# record_revb.net
KiCad netlist of a schematic drawn in EAGLE
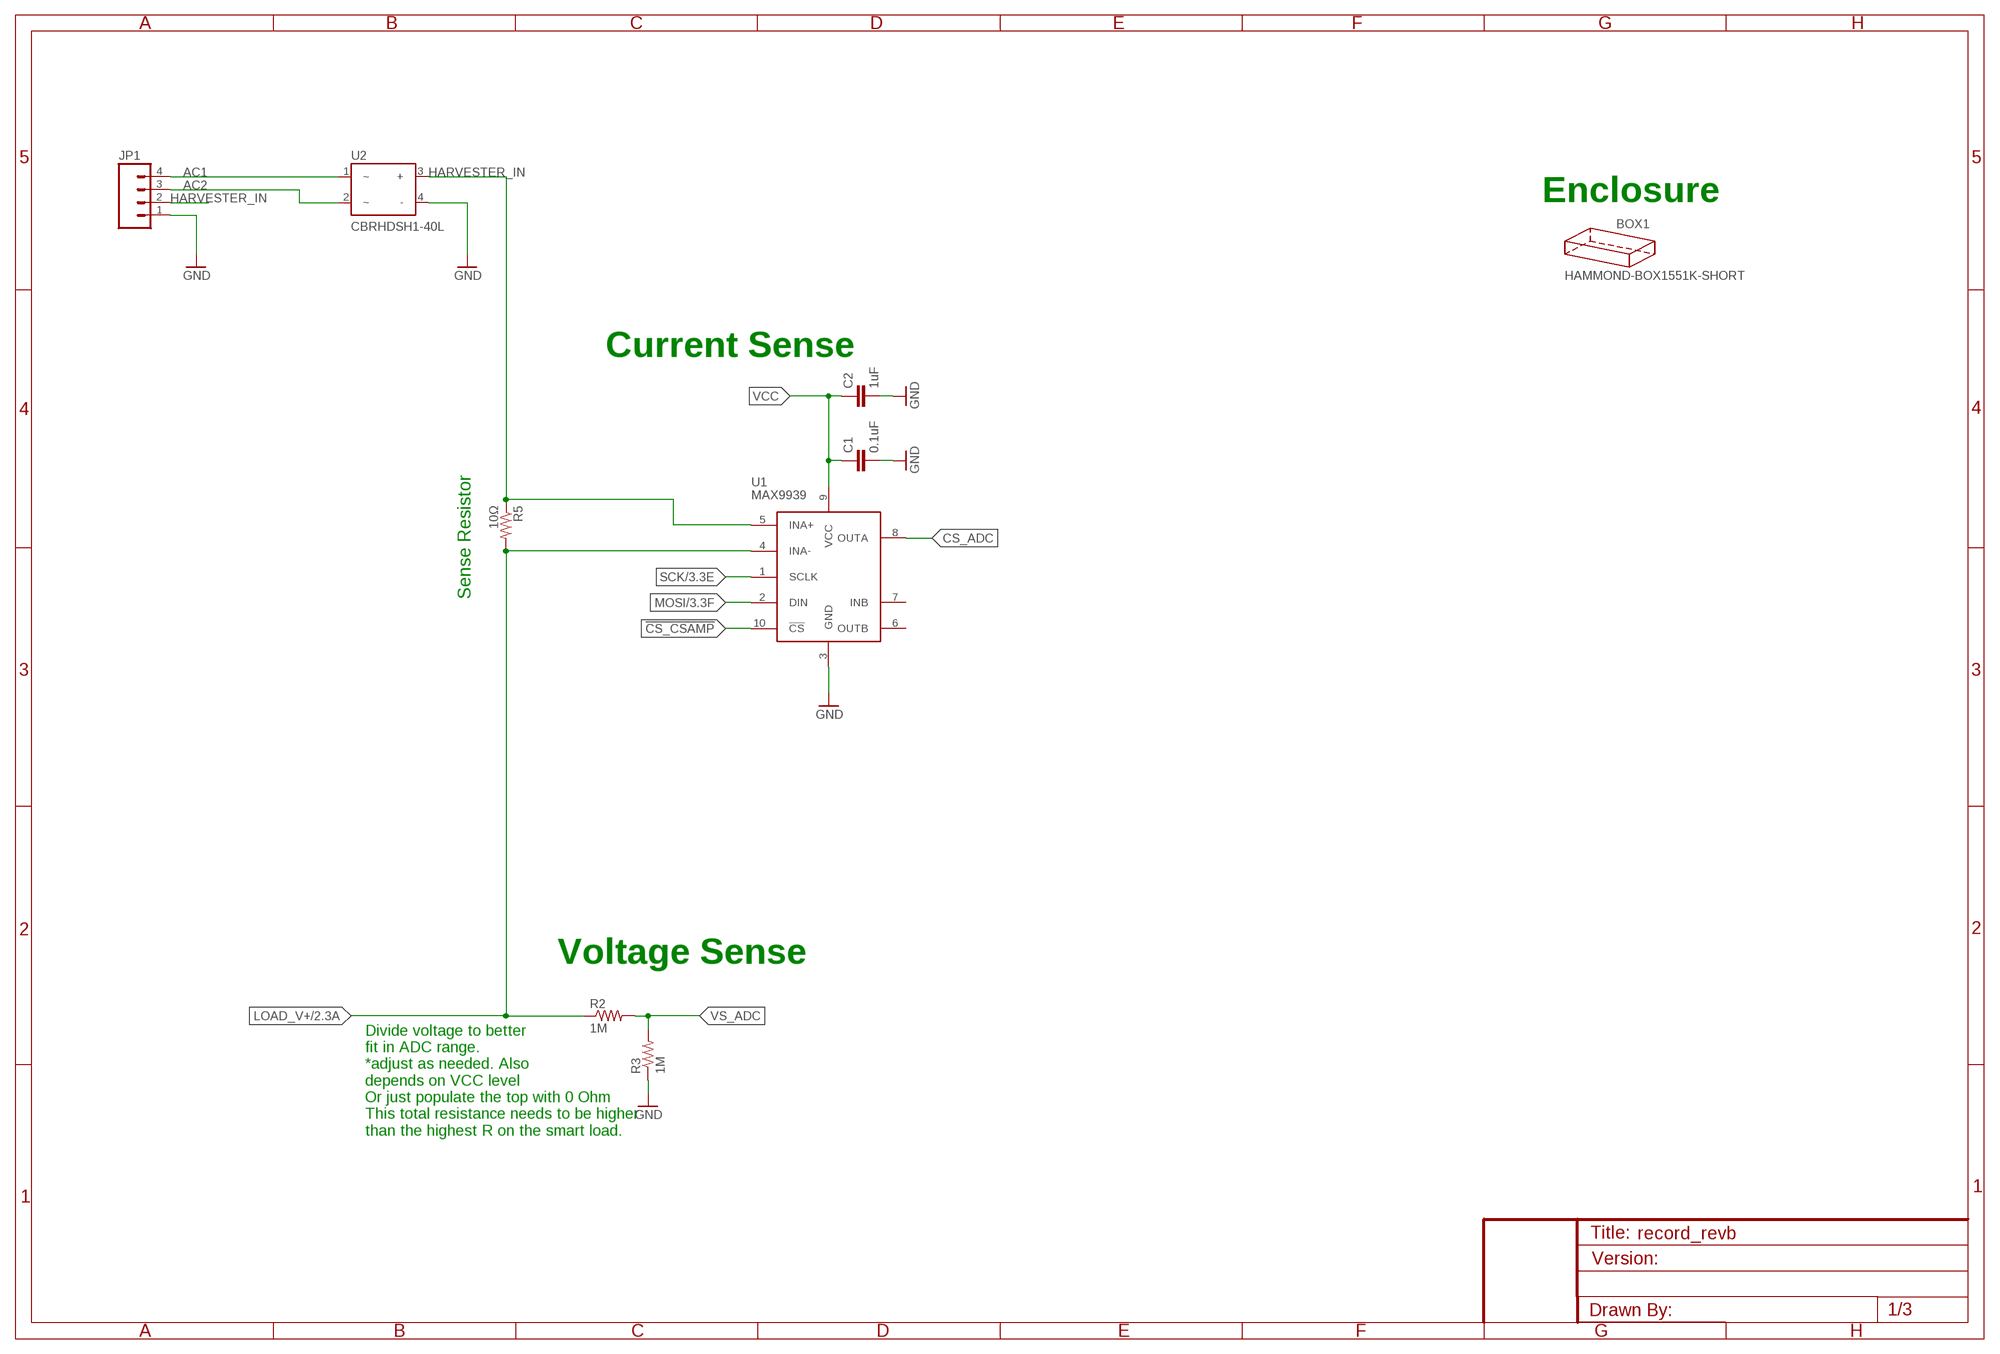
[diagram p0: schematic, sheet 1]
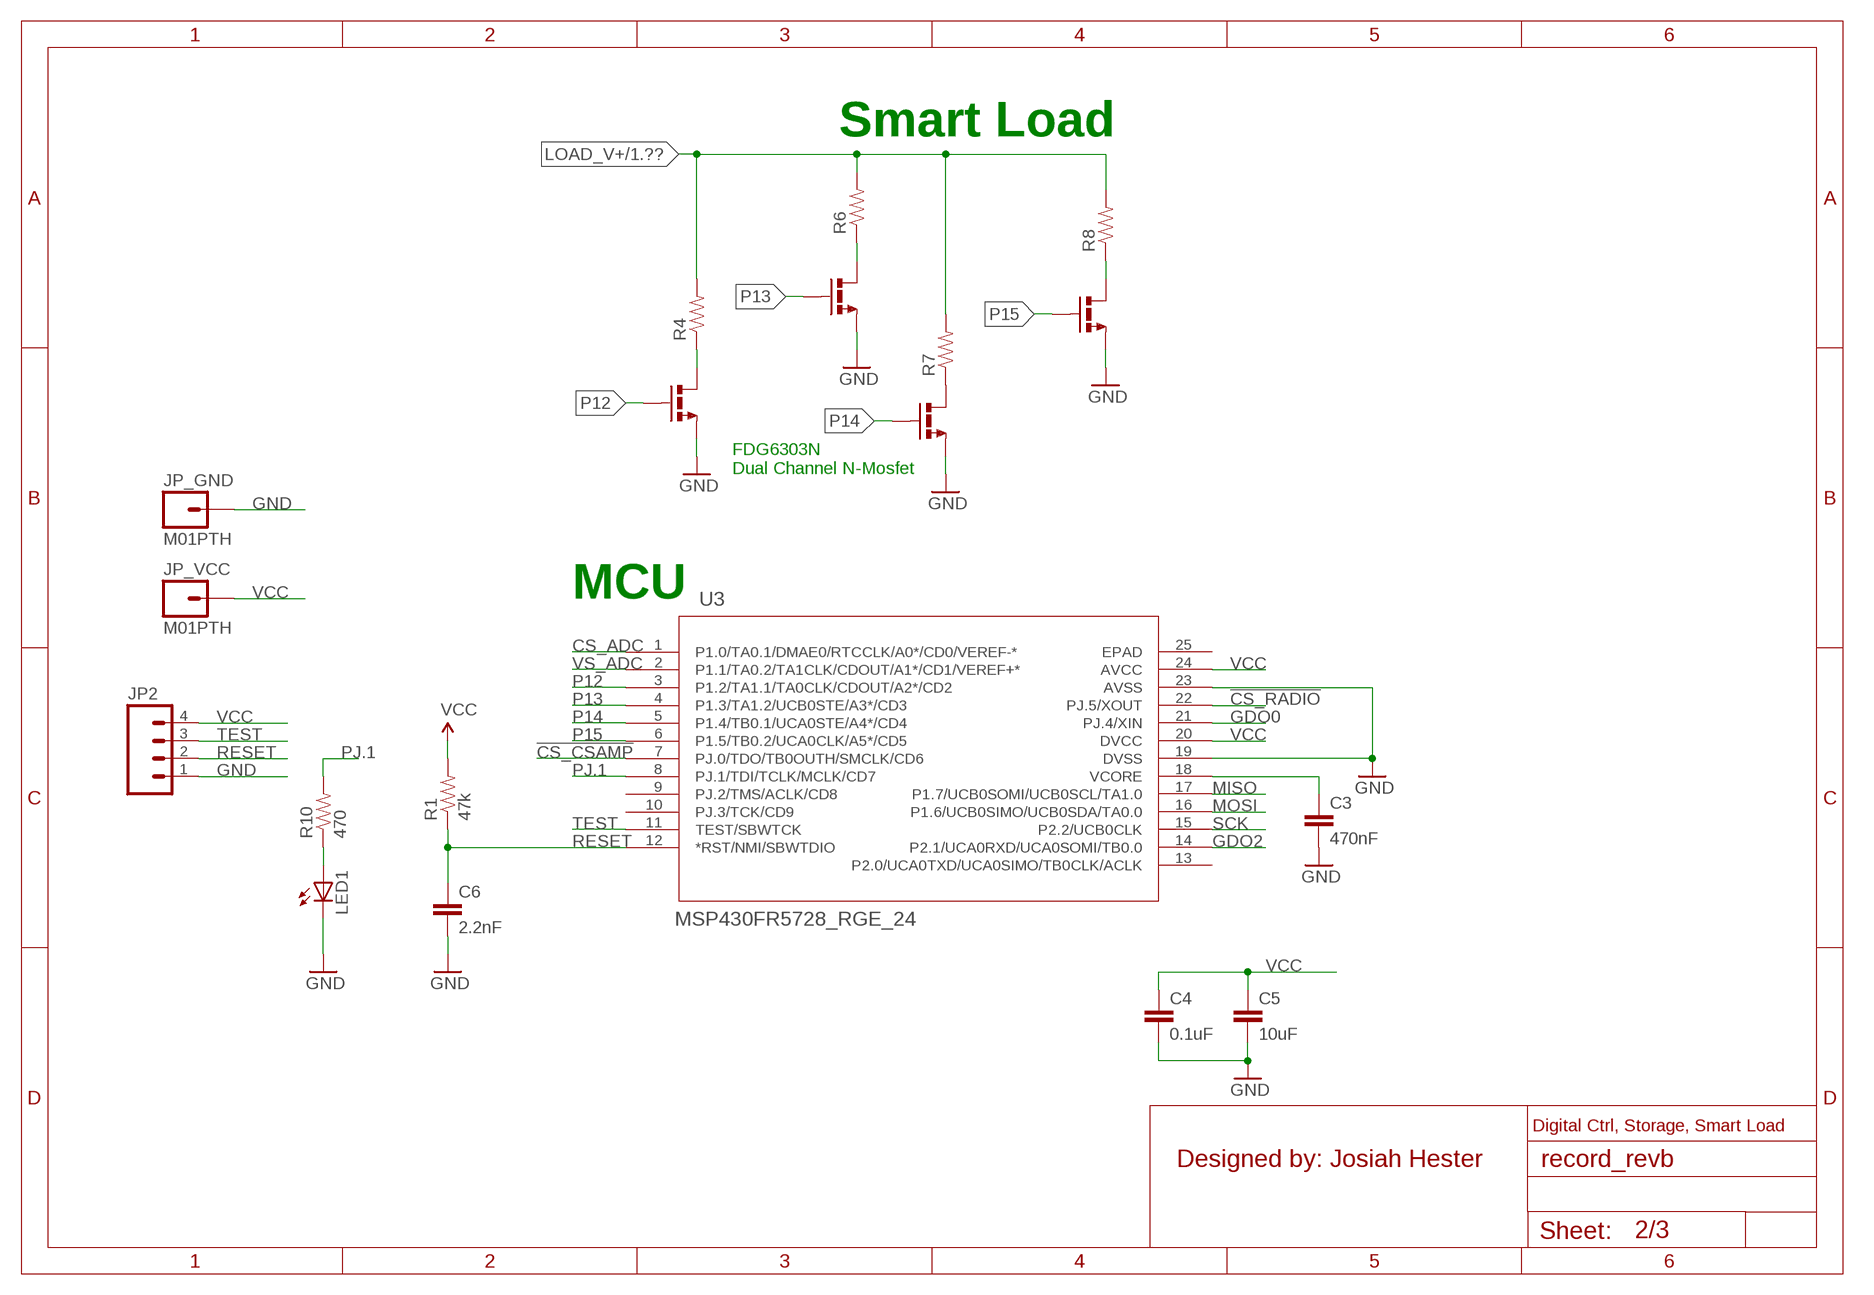
[diagram p1: schematic, sheet 2]
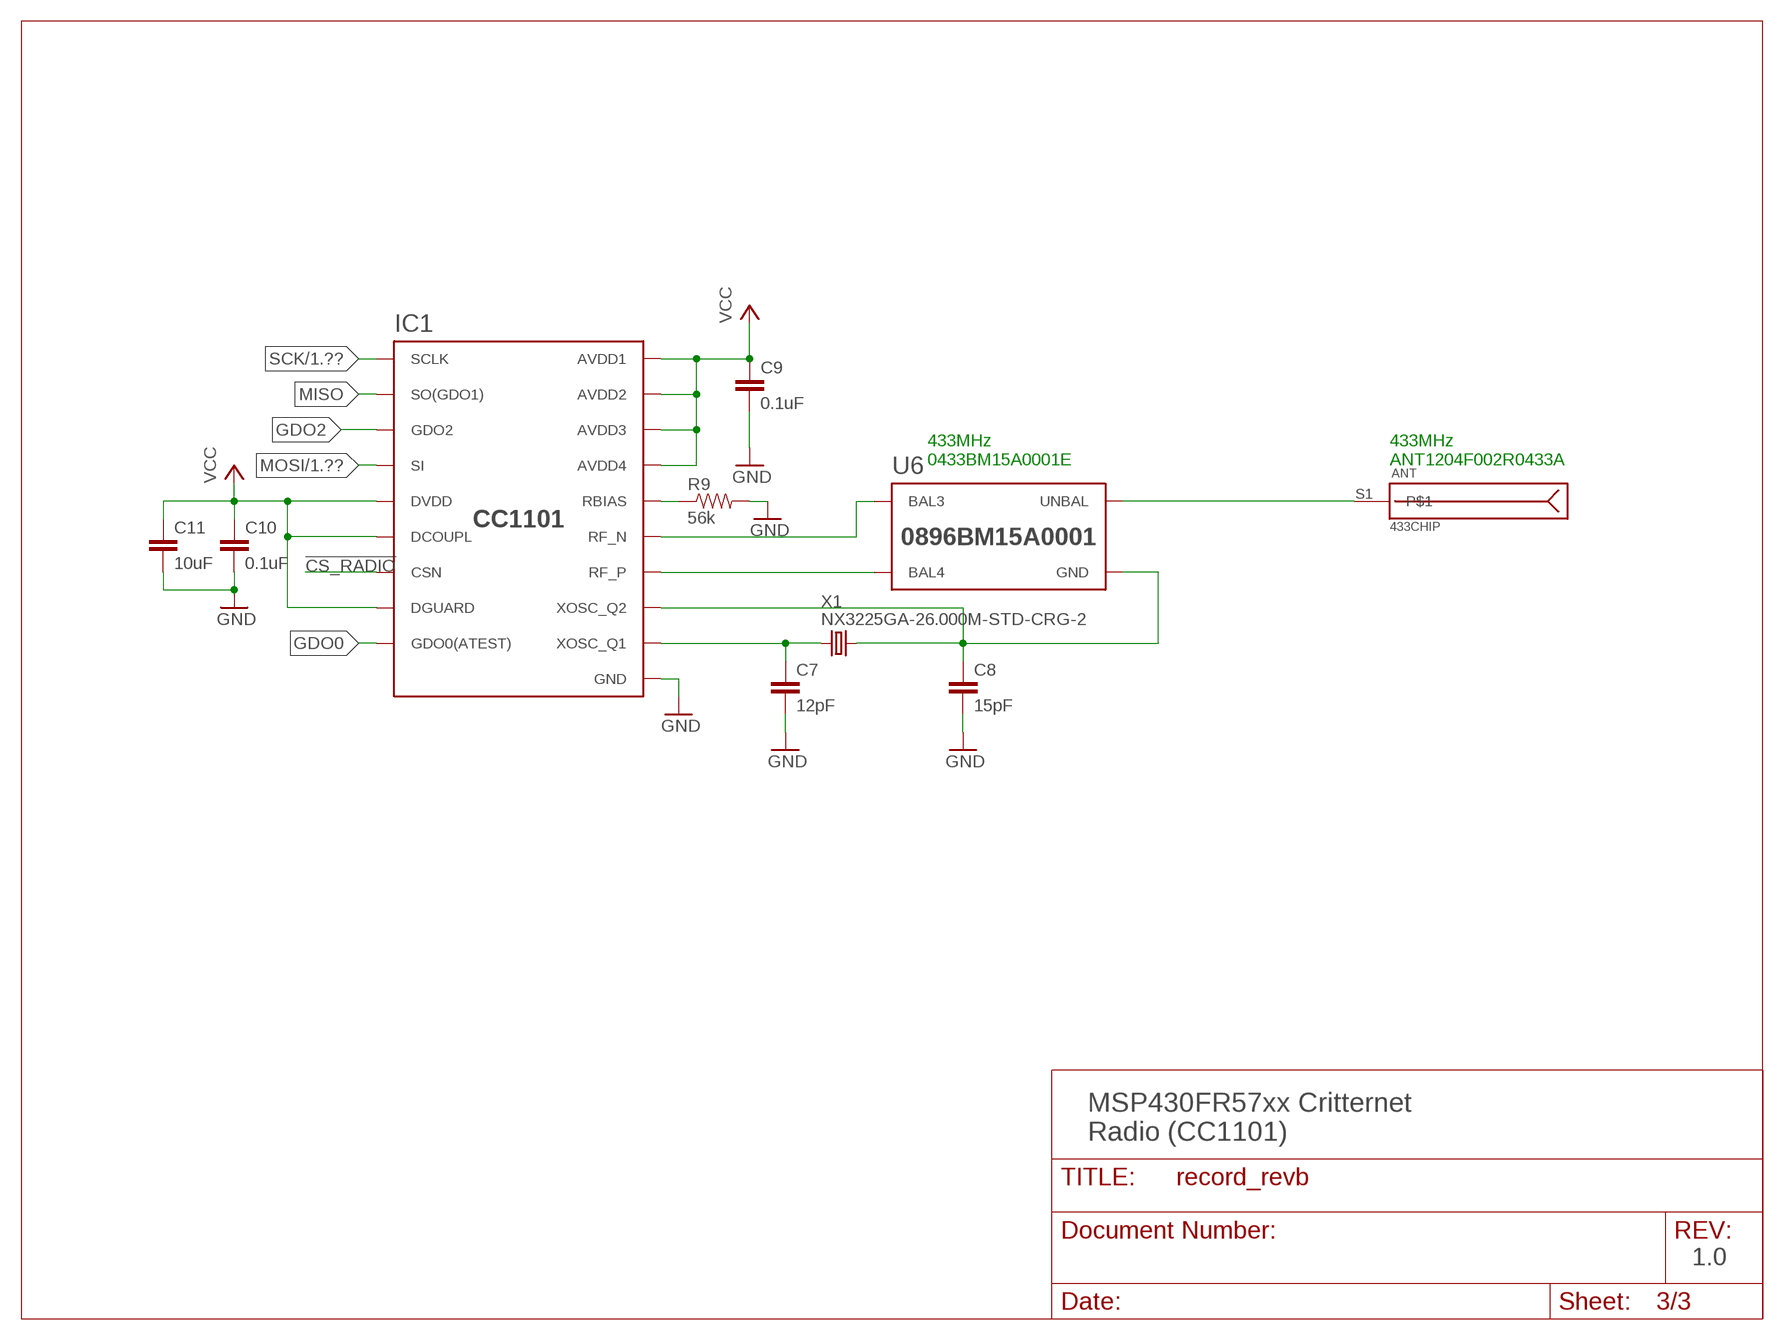
[diagram p2: schematic, sheet 3]

(export (version "E")
  (design (tool "Eeschema 10.0.6"))
  (components
    (comp (ref "BOX1")
      (value "HAMMOND-BOX1551K-SHORT")
      (footprint "eagle-import:1551K-SHORT")
      (libsource (lib "eagle-import") (part "HAMMOND-BOX1551K-SHORT"))
    )
    (comp (ref "C1")
      (value "0.1uF")
      (footprint "eagle-import:C0805")
      (libsource (lib "eagle-import") (part "CAP0805"))
    )
    (comp (ref "C2")
      (value "1uF")
      (footprint "eagle-import:C0805")
      (libsource (lib "eagle-import") (part "CAP0805"))
    )
    (comp (ref "JP1")
      (value "M04PTH")
      (footprint "eagle-import:1X04")
      (libsource (lib "eagle-import") (part "M04PTH"))
    )
    (comp (ref "R2")
      (value "1M")
      (footprint "eagle-import:0805")
      (libsource (lib "eagle-import") (part "SparkFun-Resistors_RESISTOR0805-RES"))
    )
    (comp (ref "R3")
      (value "1M")
      (footprint "eagle-import:0805")
      (libsource (lib "eagle-import") (part "SparkFun-Resistors_RESISTOR0805-RES"))
    )
    (comp (ref "R5")
      (value "10Ω")
      (footprint "eagle-import:0805")
      (libsource (lib "eagle-import") (part "RESISTOR0805-RES"))
    )
    (comp (ref "U1")
      (value "MAX9939")
      (footprint "eagle-import:10µMAX")
      (libsource (lib "eagle-import") (part "MAX9939"))
    )
    (comp (ref "U2")
      (value "CBRHDSH1-40L")
      (footprint "eagle-import:HD_DIP4")
      (libsource (lib "eagle-import") (part "CBRHDSH1-40L"))
    )
    (comp (ref "C3")
      (value "470nF")
      (footprint "eagle-import:0805")
      (libsource (lib "eagle-import") (part "1UF-25V-10%(0805)"))
    )
    (comp (ref "C4")
      (value "0.1uF")
      (footprint "eagle-import:0805")
      (libsource (lib "eagle-import") (part "1UF-25V-10%(0805)"))
    )
    (comp (ref "C5")
      (value "10uF")
      (footprint "eagle-import:0805")
      (libsource (lib "eagle-import") (part "1UF-25V-10%(0805)"))
    )
    (comp (ref "C6")
      (value "2.2nF")
      (footprint "eagle-import:0805")
      (libsource (lib "eagle-import") (part "1UF-25V-10%(0805)"))
    )
    (comp (ref "JP2")
      (value "M04PTH")
      (footprint "eagle-import:1X04")
      (libsource (lib "eagle-import") (part "M04PTH"))
    )
    (comp (ref "JP_GND")
      (value "M01PTH")
      (footprint "eagle-import:1X01")
      (libsource (lib "eagle-import") (part "M01PTH"))
    )
    (comp (ref "JP_VCC")
      (value "M01PTH")
      (footprint "eagle-import:1X01")
      (libsource (lib "eagle-import") (part "M01PTH"))
    )
    (comp (ref "LED1")
      (value "LED0603")
      (footprint "eagle-import:LED-0603")
      (libsource (lib "eagle-import") (part "LED0603"))
    )
    (comp (ref "R1")
      (value "47k")
      (footprint "eagle-import:0805")
      (libsource (lib "eagle-import") (part "0.22OHM1/4W1%(0805)"))
    )
    (comp (ref "R4")
      (value "0.22OHM1/4W1%(0805)")
      (footprint "eagle-import:0805")
      (libsource (lib "eagle-import") (part "0.22OHM1/4W1%(0805)"))
    )
    (comp (ref "R6")
      (value "0.22OHM1/4W1%(0805)")
      (footprint "eagle-import:0805")
      (libsource (lib "eagle-import") (part "0.22OHM1/4W1%(0805)"))
    )
    (comp (ref "R7")
      (value "0.22OHM1/4W1%(0805)")
      (footprint "eagle-import:0805")
      (libsource (lib "eagle-import") (part "0.22OHM1/4W1%(0805)"))
    )
    (comp (ref "R8")
      (value "0.22OHM1/4W1%(0805)")
      (footprint "eagle-import:0805")
      (libsource (lib "eagle-import") (part "0.22OHM1/4W1%(0805)"))
    )
    (comp (ref "R10")
      (value "470")
      (footprint "eagle-import:0805")
      (libsource (lib "eagle-import") (part "0.22OHM1/4W1%(0805)"))
    )
    (comp (ref "U3")
      (value "MSP430FR5728_RGE_24")
      (footprint "eagle-import:RGE24_2P1X2P1")
      (fields
        (field (name "GENERIC_PART_NUMBER") "MSP430FR5728")
        (field (name "MANUFACTURER") "Texas Instruments")
        (field (name "MANUFACTURER_PART_NUMBER") "msp430fr5728_rge_24")
      )
      (libsource (lib "eagle-import") (part "MSP430FR5728_RGE_24"))
    )
    (comp (ref "U4")
      (value "FDG6303N")
      (footprint "eagle-import:SC70-6")
      (libsource (lib "eagle-import") (part "FDG6303N"))
    )
    (comp (ref "U5")
      (value "FDG6303N")
      (footprint "eagle-import:SC70-6")
      (libsource (lib "eagle-import") (part "FDG6303N"))
    )
    (comp (ref "ANT")
      (value "433CHIP")
      (footprint "eagle-import:ANT-433-USP")
      (libsource (lib "eagle-import") (part "433CHIP"))
    )
    (comp (ref "C7")
      (value "12pF")
      (footprint "eagle-import:0603-CAP")
      (libsource (lib "eagle-import") (part "0.1UF-25V(+80/-20%)(0603)"))
    )
    (comp (ref "C8")
      (value "15pF")
      (footprint "eagle-import:0603-CAP")
      (libsource (lib "eagle-import") (part "0.1UF-25V(+80/-20%)(0603)"))
    )
    (comp (ref "C9")
      (value "0.1uF")
      (footprint "eagle-import:0603-CAP")
      (libsource (lib "eagle-import") (part "CAP0603-CAP"))
    )
    (comp (ref "C10")
      (value "0.1uF")
      (footprint "eagle-import:C0805")
      (libsource (lib "eagle-import") (part "CAP0805"))
    )
    (comp (ref "C11")
      (value "10uF")
      (footprint "eagle-import:0805")
      (libsource (lib "eagle-import") (part "1.0UF-25V-+80/-20(0805)"))
    )
    (comp (ref "IC1")
      (value "CC1101")
      (footprint "eagle-import:QLP20")
      (libsource (lib "eagle-import") (part "CC1101"))
    )
    (comp (ref "R9")
      (value "56k")
      (footprint "eagle-import:0603")
      (libsource (lib "eagle-import") (part "0OHM1/10W5%(0603)"))
    )
    (comp (ref "U6")
      (value "0896BM15A0001")
      (footprint "eagle-import:0896BM15A0001")
      (libsource (lib "eagle-import") (part "0896BM15A0001"))
    )
    (comp (ref "X1")
      (value "NX3225GA-26.000M-STD-CRG-2")
      (footprint "eagle-import:XTAL-3.2X2.5")
      (libsource (lib "eagle-import") (part "XTAL-3.2X2.5"))
    )
  )
  (nets
    (net (code "1") (name "AC1") (class "Default")
      (node (ref "JP1") (pin "4") (pinfunction "4_4") (pintype "passive"))
      (node (ref "U2") (pin "1") (pinfunction "~_1") (pintype "bidirectional"))
    )
    (net (code "2") (name "AC2") (class "Default")
      (node (ref "JP1") (pin "3") (pinfunction "3_3") (pintype "passive"))
      (node (ref "U2") (pin "2") (pinfunction "~_2") (pintype "bidirectional"))
    )
    (net (code "3") (name "CS_ADC") (class "Default")
      (node (ref "U1") (pin "8") (pinfunction "OUTA_8") (pintype "bidirectional"))
      (node (ref "U3") (pin "1") (pinfunction "P1.0/TA0.1/DMAE0/RTCCLK/A0*/CD0/VEREF-*_1") (pintype "bidirectional"))
    )
    (net (code "4") (name "GDO0") (class "Default")
      (node (ref "IC1") (pin "6") (pinfunction "GDO0(ATEST)_6") (pintype "bidirectional"))
      (node (ref "U3") (pin "21") (pinfunction "PJ.4/XIN_21") (pintype "bidirectional"))
    )
    (net (code "5") (name "GDO2") (class "Default")
      (node (ref "IC1") (pin "3") (pinfunction "GDO2_3") (pintype "bidirectional"))
      (node (ref "U3") (pin "14") (pinfunction "P2.1/UCA0RXD/UCA0SOMI/TB0.0_14") (pintype "bidirectional"))
    )
    (net (code "6") (name "GND") (class "Default")
      (node (ref "C1") (pin "2") (pinfunction "2_2") (pintype "passive"))
      (node (ref "C10") (pin "2") (pinfunction "2_2") (pintype "passive"))
      (node (ref "C11") (pin "2") (pinfunction "2_2") (pintype "passive"))
      (node (ref "C2") (pin "2") (pinfunction "2_2") (pintype "passive"))
      (node (ref "C3") (pin "2") (pinfunction "2_2") (pintype "passive"))
      (node (ref "C4") (pin "2") (pinfunction "2_2") (pintype "passive"))
      (node (ref "C5") (pin "2") (pinfunction "2_2") (pintype "passive"))
      (node (ref "C6") (pin "2") (pinfunction "2_2") (pintype "passive"))
      (node (ref "C7") (pin "2") (pinfunction "2_2") (pintype "passive"))
      (node (ref "C8") (pin "2") (pinfunction "2_2") (pintype "passive"))
      (node (ref "C9") (pin "2") (pinfunction "2_2") (pintype "passive"))
      (node (ref "IC1") (pin "16") (pinfunction "GND_16") (pintype "bidirectional"))
      (node (ref "IC1") (pin "19") (pinfunction "GND_19") (pintype "bidirectional"))
      (node (ref "IC1") (pin "GND") (pinfunction "GND_GND") (pintype "bidirectional"))
      (node (ref "IC1") (pin "GND1") (pinfunction "GND_GND1") (pintype "bidirectional"))
      (node (ref "IC1") (pin "GND2") (pinfunction "GND_GND2") (pintype "bidirectional"))
      (node (ref "IC1") (pin "GND3") (pinfunction "GND_GND3") (pintype "bidirectional"))
      (node (ref "IC1") (pin "GND4") (pinfunction "GND_GND4") (pintype "bidirectional"))
      (node (ref "IC1") (pin "GND5") (pinfunction "GND_GND5") (pintype "bidirectional"))
      (node (ref "JP1") (pin "1") (pinfunction "1_1") (pintype "passive"))
      (node (ref "JP2") (pin "1") (pinfunction "1_1") (pintype "passive"))
      (node (ref "JP_GND") (pin "1") (pinfunction "1_1") (pintype "passive"))
      (node (ref "LED1") (pin "C") (pinfunction "C_C") (pintype "passive"))
      (node (ref "R3") (pin "1") (pinfunction "1_1") (pintype "passive"))
      (node (ref "R9") (pin "2") (pinfunction "2_2") (pintype "passive"))
      (node (ref "U1") (pin "3") (pinfunction "GND_3") (pintype "bidirectional"))
      (node (ref "U2") (pin "4") (pinfunction "-_4") (pintype "bidirectional"))
      (node (ref "U3") (pin "19") (pinfunction "DVSS_19") (pintype "power_in"))
      (node (ref "U3") (pin "23") (pinfunction "AVSS_23") (pintype "power_in"))
      (node (ref "U4") (pin "1") (pinfunction "S2_1") (pintype "passive"))
      (node (ref "U4") (pin "4") (pinfunction "S1_4") (pintype "passive"))
      (node (ref "U5") (pin "1") (pinfunction "S2_1") (pintype "passive"))
      (node (ref "U5") (pin "4") (pinfunction "S1_4") (pintype "passive"))
    )
    (net (code "7") (name "HARVESTER_IN") (class "Default")
      (node (ref "JP1") (pin "2") (pinfunction "2_2") (pintype "passive"))
      (node (ref "R5") (pin "1") (pinfunction "1_1") (pintype "passive"))
      (node (ref "U1") (pin "5") (pinfunction "INA+_5") (pintype "bidirectional"))
      (node (ref "U2") (pin "3") (pinfunction "+_3") (pintype "bidirectional"))
    )
    (net (code "8") (name "LOAD_V+") (class "Default")
      (node (ref "R2") (pin "1") (pinfunction "1_1") (pintype "passive"))
      (node (ref "R4") (pin "2") (pinfunction "2_2") (pintype "passive"))
      (node (ref "R5") (pin "2") (pinfunction "2_2") (pintype "passive"))
      (node (ref "R6") (pin "2") (pinfunction "2_2") (pintype "passive"))
      (node (ref "R7") (pin "2") (pinfunction "2_2") (pintype "passive"))
      (node (ref "R8") (pin "2") (pinfunction "2_2") (pintype "passive"))
      (node (ref "U1") (pin "4") (pinfunction "INA-_4") (pintype "bidirectional"))
    )
    (net (code "9") (name "MISO") (class "Default")
      (node (ref "IC1") (pin "2") (pinfunction "SO(GDO1)_2") (pintype "bidirectional"))
      (node (ref "U3") (pin "17") (pinfunction "P1.7/UCB0SOMI/UCB0SCL/TA1.0_17") (pintype "bidirectional"))
    )
    (net (code "10") (name "MOSI") (class "Default")
      (node (ref "IC1") (pin "20") (pinfunction "SI_20") (pintype "bidirectional"))
      (node (ref "U1") (pin "2") (pinfunction "DIN_2") (pintype "bidirectional"))
      (node (ref "U3") (pin "16") (pinfunction "P1.6/UCB0SIMO/UCB0SDA/TA0.0_16") (pintype "bidirectional"))
    )
    (net (code "11") (name "Net-(ANT-P$1)") (class "Default")
      (node (ref "ANT") (pin "S1") (pinfunction "P$1_S1") (pintype "bidirectional"))
      (node (ref "U6") (pin "1") (pinfunction "UNBAL_1") (pintype "bidirectional"))
    )
    (net (code "12") (name "Net-(IC1-RBIAS)") (class "Default")
      (node (ref "IC1") (pin "17") (pinfunction "RBIAS_17") (pintype "bidirectional"))
      (node (ref "R9") (pin "1") (pinfunction "1_1") (pintype "passive"))
    )
    (net (code "13") (name "Net-(IC1-RF_N)") (class "Default")
      (node (ref "IC1") (pin "13") (pinfunction "RF_N_13") (pintype "bidirectional"))
      (node (ref "U6") (pin "3") (pinfunction "BAL3_3") (pintype "bidirectional"))
    )
    (net (code "14") (name "Net-(IC1-RF_P)") (class "Default")
      (node (ref "IC1") (pin "12") (pinfunction "RF_P_12") (pintype "bidirectional"))
      (node (ref "U6") (pin "4") (pinfunction "BAL4_4") (pintype "bidirectional"))
    )
    (net (code "15") (name "Net-(IC1-XOSC_Q1)") (class "Default")
      (node (ref "C7") (pin "1") (pinfunction "1_1") (pintype "passive"))
      (node (ref "IC1") (pin "8") (pinfunction "XOSC_Q1_8") (pintype "bidirectional"))
      (node (ref "X1") (pin "1") (pinfunction "1_1") (pintype "passive"))
    )
    (net (code "16") (name "Net-(IC1-XOSC_Q2)") (class "Default")
      (node (ref "C8") (pin "1") (pinfunction "1_1") (pintype "passive"))
      (node (ref "IC1") (pin "10") (pinfunction "XOSC_Q2_10") (pintype "bidirectional"))
      (node (ref "U6") (pin "2") (pinfunction "GND_2") (pintype "bidirectional"))
      (node (ref "U6") (pin "5") (pinfunction "GND_5") (pintype "bidirectional"))
      (node (ref "U6") (pin "6") (pinfunction "GND_6") (pintype "bidirectional"))
      (node (ref "X1") (pin "3") (pinfunction "2_3") (pintype "passive"))
    )
    (net (code "17") (name "Net-(LED1-PadA)") (class "Default")
      (node (ref "LED1") (pin "A") (pinfunction "A_A") (pintype "passive"))
      (node (ref "R10") (pin "1") (pinfunction "1_1") (pintype "passive"))
    )
    (net (code "18") (name "Net-(U3-VCORE)") (class "Default")
      (node (ref "C3") (pin "1") (pinfunction "1_1") (pintype "passive"))
      (node (ref "U3") (pin "18") (pinfunction "VCORE_18") (pintype "power_in"))
    )
    (net (code "19") (name "Net-(U4-D1)") (class "Default")
      (node (ref "R4") (pin "1") (pinfunction "1_1") (pintype "passive"))
      (node (ref "U4") (pin "3") (pinfunction "D1_3") (pintype "passive"))
    )
    (net (code "20") (name "Net-(U4-D2)") (class "Default")
      (node (ref "R6") (pin "1") (pinfunction "1_1") (pintype "passive"))
      (node (ref "U4") (pin "6") (pinfunction "D2_6") (pintype "passive"))
    )
    (net (code "21") (name "Net-(U5-D1)") (class "Default")
      (node (ref "R7") (pin "1") (pinfunction "1_1") (pintype "passive"))
      (node (ref "U5") (pin "3") (pinfunction "D1_3") (pintype "passive"))
    )
    (net (code "22") (name "Net-(U5-D2)") (class "Default")
      (node (ref "R8") (pin "1") (pinfunction "1_1") (pintype "passive"))
      (node (ref "U5") (pin "6") (pinfunction "D2_6") (pintype "passive"))
    )
    (net (code "23") (name "P12") (class "Default")
      (node (ref "U3") (pin "3") (pinfunction "P1.2/TA1.1/TA0CLK/CDOUT/A2*/CD2_3") (pintype "bidirectional"))
      (node (ref "U4") (pin "5") (pinfunction "G1_5") (pintype "passive"))
    )
    (net (code "24") (name "P13") (class "Default")
      (node (ref "U3") (pin "4") (pinfunction "P1.3/TA1.2/UCB0STE/A3*/CD3_4") (pintype "bidirectional"))
      (node (ref "U4") (pin "2") (pinfunction "G2_2") (pintype "passive"))
    )
    (net (code "25") (name "P14") (class "Default")
      (node (ref "U3") (pin "5") (pinfunction "P1.4/TB0.1/UCA0STE/A4*/CD4_5") (pintype "bidirectional"))
      (node (ref "U5") (pin "5") (pinfunction "G1_5") (pintype "passive"))
    )
    (net (code "26") (name "P15") (class "Default")
      (node (ref "U3") (pin "6") (pinfunction "P1.5/TB0.2/UCA0CLK/A5*/CD5_6") (pintype "bidirectional"))
      (node (ref "U5") (pin "2") (pinfunction "G2_2") (pintype "passive"))
    )
    (net (code "27") (name "PJ.1") (class "Default")
      (node (ref "R10") (pin "2") (pinfunction "2_2") (pintype "passive"))
      (node (ref "U3") (pin "8") (pinfunction "PJ.1/TDI/TCLK/MCLK/CD7_8") (pintype "bidirectional"))
    )
    (net (code "28") (name "RESET") (class "Default")
      (node (ref "C6") (pin "1") (pinfunction "1_1") (pintype "passive"))
      (node (ref "JP2") (pin "2") (pinfunction "2_2") (pintype "passive"))
      (node (ref "R1") (pin "1") (pinfunction "1_1") (pintype "passive"))
      (node (ref "U3") (pin "12") (pinfunction "*RST/NMI/SBWTDIO_12") (pintype "bidirectional"))
    )
    (net (code "29") (name "SCK") (class "Default")
      (node (ref "IC1") (pin "1") (pinfunction "SCLK_1") (pintype "bidirectional"))
      (node (ref "U1") (pin "1") (pinfunction "SCLK_1") (pintype "bidirectional"))
      (node (ref "U3") (pin "15") (pinfunction "P2.2/UCB0CLK_15") (pintype "bidirectional"))
    )
    (net (code "30") (name "TEST") (class "Default")
      (node (ref "JP2") (pin "3") (pinfunction "3_3") (pintype "passive"))
      (node (ref "U3") (pin "11") (pinfunction "TEST/SBWTCK_11") (pintype "bidirectional"))
    )
    (net (code "31") (name "VCC") (class "Default")
      (node (ref "C1") (pin "1") (pinfunction "1_1") (pintype "passive"))
      (node (ref "C10") (pin "1") (pinfunction "1_1") (pintype "passive"))
      (node (ref "C11") (pin "1") (pinfunction "1_1") (pintype "passive"))
      (node (ref "C2") (pin "1") (pinfunction "1_1") (pintype "passive"))
      (node (ref "C4") (pin "1") (pinfunction "1_1") (pintype "passive"))
      (node (ref "C5") (pin "1") (pinfunction "1_1") (pintype "passive"))
      (node (ref "C9") (pin "1") (pinfunction "1_1") (pintype "passive"))
      (node (ref "IC1") (pin "11") (pinfunction "AVDD2_11") (pintype "bidirectional"))
      (node (ref "IC1") (pin "14") (pinfunction "AVDD3_14") (pintype "bidirectional"))
      (node (ref "IC1") (pin "15") (pinfunction "AVDD4_15") (pintype "bidirectional"))
      (node (ref "IC1") (pin "18") (pinfunction "DGUARD_18") (pintype "bidirectional"))
      (node (ref "IC1") (pin "4") (pinfunction "DVDD_4") (pintype "bidirectional"))
      (node (ref "IC1") (pin "5") (pinfunction "DCOUPL_5") (pintype "bidirectional"))
      (node (ref "IC1") (pin "9") (pinfunction "AVDD1_9") (pintype "bidirectional"))
      (node (ref "JP2") (pin "4") (pinfunction "4_4") (pintype "passive"))
      (node (ref "JP_VCC") (pin "1") (pinfunction "1_1") (pintype "passive"))
      (node (ref "R1") (pin "2") (pinfunction "2_2") (pintype "passive"))
      (node (ref "U1") (pin "9") (pinfunction "VCC_9") (pintype "bidirectional"))
      (node (ref "U3") (pin "20") (pinfunction "DVCC_20") (pintype "power_in"))
      (node (ref "U3") (pin "24") (pinfunction "AVCC_24") (pintype "power_in"))
    )
    (net (code "32") (name "VS_ADC") (class "Default")
      (node (ref "R2") (pin "2") (pinfunction "2_2") (pintype "passive"))
      (node (ref "R3") (pin "2") (pinfunction "2_2") (pintype "passive"))
      (node (ref "U3") (pin "2") (pinfunction "P1.1/TA0.2/TA1CLK/CDOUT/A1*/CD1/VEREF+*_2") (pintype "bidirectional"))
    )
    (net (code "33") (name "unconnected-(U1-INB-Pad7)") (class "Default")
      (node (ref "U1") (pin "7") (pinfunction "INB_7") (pintype "bidirectional"))
    )
    (net (code "34") (name "unconnected-(U1-OUTB-Pad6)") (class "Default")
      (node (ref "U1") (pin "6") (pinfunction "OUTB_6") (pintype "bidirectional"))
    )
    (net (code "35") (name "unconnected-(U3-EPAD-Pad25)") (class "Default")
      (node (ref "U3") (pin "25") (pinfunction "EPAD_25") (pintype "passive"))
    )
    (net (code "36") (name "unconnected-(U3-P2.0{slash}UCA0TXD{slash}UCA0SIMO{slash}TB0CLK{slash}ACLK-Pad13)") (class "Default")
      (node (ref "U3") (pin "13") (pinfunction "P2.0/UCA0TXD/UCA0SIMO/TB0CLK/ACLK_13") (pintype "bidirectional"))
    )
    (net (code "37") (name "unconnected-(U3-PJ.2{slash}TMS{slash}ACLK{slash}CD8-Pad9)") (class "Default")
      (node (ref "U3") (pin "9") (pinfunction "PJ.2/TMS/ACLK/CD8_9") (pintype "bidirectional"))
    )
    (net (code "38") (name "unconnected-(U3-PJ.3{slash}TCK{slash}CD9-Pad10)") (class "Default")
      (node (ref "U3") (pin "10") (pinfunction "PJ.3/TCK/CD9_10") (pintype "bidirectional"))
    )
    (net (code "39") (name "~{CS_CSAMP}") (class "Default")
      (node (ref "U1") (pin "10") (pinfunction "~{CS}_10") (pintype "bidirectional"))
      (node (ref "U3") (pin "7") (pinfunction "PJ.0/TDO/TB0OUTH/SMCLK/CD6_7") (pintype "bidirectional"))
    )
    (net (code "40") (name "~{CS_RADIO}") (class "Default")
      (node (ref "IC1") (pin "7") (pinfunction "CSN_7") (pintype "bidirectional"))
      (node (ref "U3") (pin "22") (pinfunction "PJ.5/XOUT_22") (pintype "bidirectional"))
    )
  )
)
